# ADE7753.net
KiCad netlist of a schematic drawn in Altium Designer
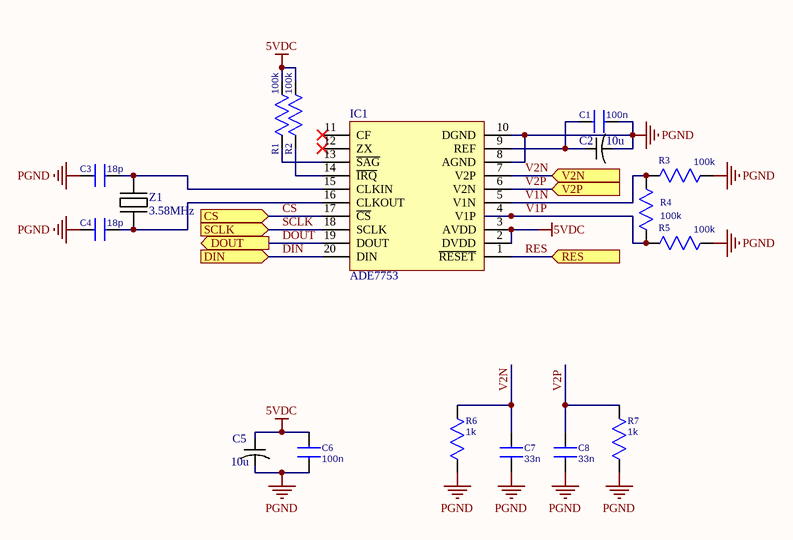
[diagram p0: ADE7753.SchDoc]

(export (version "E")
  (design (tool "Eeschema 10.0.6"))
  (components
    (comp (ref "C1")
      (value "100n")
      (footprint "C_0603")
      (description "Capacitor")
      (libsource (lib "AX_Altium_v2.3") (part "C0603"))
    )
    (comp (ref "C2")
      (value "10u")
      (footprint "TANTALUM_CAP_SIZE_A")
      (description "Tantalum Capacitor")
      (libsource (lib "BublykIntegratedLibrary") (part "Tantalum Capacitor"))
    )
    (comp (ref "C3")
      (value "18p")
      (footprint "C_0603")
      (description "Capacitor")
      (libsource (lib "AX_Altium_v2.3") (part "C0603"))
    )
    (comp (ref "C4")
      (value "18p")
      (footprint "C_0603")
      (description "Capacitor")
      (libsource (lib "AX_Altium_v2.3") (part "C0603"))
    )
    (comp (ref "C5")
      (value "10u")
      (footprint "TANTALUM_CAP_SIZE_A")
      (description "Tantalum Capacitor")
      (libsource (lib "") (part "Tantalum Capacitor_1"))
    )
    (comp (ref "C6")
      (value "100n")
      (footprint "C_0603")
      (description "Capacitor")
      (libsource (lib "AX_Altium_v2.3") (part "C0603"))
    )
    (comp (ref "C7")
      (value "33n")
      (footprint "C_0603")
      (description "Capacitor")
      (libsource (lib "AX_Altium_v2.3") (part "C0603"))
    )
    (comp (ref "C8")
      (value "33n")
      (footprint "C_0603")
      (description "Capacitor")
      (libsource (lib "AX_Altium_v2.3") (part "C0603"))
    )
    (comp (ref "IC1")
      (value "ADE7753")
      (footprint "SOP-20")
      (description "Data Acquisition ADC/DAC")
      (libsource (lib "SmartOutletIntegratedLibrary") (part "ADE7753ARSZ"))
    )
    (comp (ref "R1")
      (value "100k")
      (footprint "R_0603")
      (description "Resistor")
      (libsource (lib "AX_Altium_v2.3") (part "R0603"))
    )
    (comp (ref "R2")
      (value "100k")
      (footprint "R_0603")
      (description "Resistor")
      (libsource (lib "AX_Altium_v2.3") (part "R0603"))
    )
    (comp (ref "R3")
      (value "100k")
      (footprint "R_0603")
      (description "Resistor")
      (libsource (lib "AX_Altium_v2.3") (part "R0603"))
    )
    (comp (ref "R4")
      (value "100k")
      (footprint "R_0603")
      (description "Resistor")
      (libsource (lib "AX_Altium_v2.3") (part "R0603"))
    )
    (comp (ref "R5")
      (value "100k")
      (footprint "R_0603")
      (description "Resistor")
      (libsource (lib "AX_Altium_v2.3") (part "R0603"))
    )
    (comp (ref "R6")
      (value "1k")
      (footprint "R_0603")
      (description "Resistor")
      (libsource (lib "AX_Altium_v2.3") (part "R0603"))
    )
    (comp (ref "R7")
      (value "1k")
      (footprint "R_0805")
      (description "Resistor")
      (libsource (lib "AX_Altium_v2.3") (part "R0805"))
    )
    (comp (ref "Z1")
      (value "3.58MHz")
      (footprint "HC-49")
      (description "Quartz resonator")
      (libsource (lib "Light_Music_Integrated_Library") (part "XTAL"))
    )
  )
  (nets
    (net (code "1") (name "/CS") (class "Default")
      (node (ref "IC1") (pin "17") (pinfunction "~{CS}_17") (pintype "passive"))
    )
    (net (code "2") (name "/DIN") (class "Default")
      (node (ref "IC1") (pin "20") (pinfunction "DIN_20") (pintype "passive"))
    )
    (net (code "3") (name "/DOUT") (class "Default")
      (node (ref "IC1") (pin "19") (pinfunction "DOUT_19") (pintype "passive"))
    )
    (net (code "4") (name "/RES") (class "Default")
      (node (ref "IC1") (pin "1") (pinfunction "~{RESET}_1") (pintype "passive"))
    )
    (net (code "5") (name "/SCLK") (class "Default")
      (node (ref "IC1") (pin "18") (pinfunction "SCLK_18") (pintype "passive"))
    )
    (net (code "6") (name "/V1N") (class "Default")
      (node (ref "IC1") (pin "5") (pinfunction "V1N_5") (pintype "passive"))
      (node (ref "R3") (pin "2") (pintype "passive"))
      (node (ref "R4") (pin "2") (pintype "passive"))
    )
    (net (code "7") (name "/V1P") (class "Default")
      (node (ref "IC1") (pin "4") (pinfunction "V1P_4") (pintype "passive"))
      (node (ref "R4") (pin "1") (pintype "passive"))
      (node (ref "R5") (pin "2") (pintype "passive"))
    )
    (net (code "8") (name "/V2N") (class "Default")
      (node (ref "C7") (pin "2") (pintype "passive"))
      (node (ref "IC1") (pin "7") (pinfunction "V2P_7") (pintype "passive"))
      (node (ref "R6") (pin "1") (pintype "passive"))
    )
    (net (code "9") (name "/V2P") (class "Default")
      (node (ref "C8") (pin "2") (pintype "passive"))
      (node (ref "IC1") (pin "6") (pinfunction "V2N_6") (pintype "passive"))
      (node (ref "R7") (pin "1") (pintype "passive"))
    )
    (net (code "10") (name "5VDC") (class "Default")
      (node (ref "C5") (pin "1") (pinfunction "1_1") (pintype "passive"))
      (node (ref "C6") (pin "2") (pintype "passive"))
      (node (ref "IC1") (pin "2") (pinfunction "DVDD_2") (pintype "passive"))
      (node (ref "IC1") (pin "3") (pinfunction "AVDD_3") (pintype "passive"))
      (node (ref "R1") (pin "2") (pintype "passive"))
      (node (ref "R2") (pin "2") (pintype "passive"))
    )
    (net (code "11") (name "Net-(IC1-CLKIN)") (class "Default")
      (node (ref "C3") (pin "2") (pintype "passive"))
      (node (ref "IC1") (pin "15") (pinfunction "CLKIN_15") (pintype "passive"))
      (node (ref "Z1") (pin "2") (pinfunction "2_2") (pintype "passive"))
    )
    (net (code "12") (name "Net-(IC1-CLKOUT)") (class "Default")
      (node (ref "C4") (pin "2") (pintype "passive"))
      (node (ref "IC1") (pin "16") (pinfunction "CLKOUT_16") (pintype "passive"))
      (node (ref "Z1") (pin "1") (pinfunction "1_1") (pintype "passive"))
    )
    (net (code "13") (name "Net-(IC1-REF)") (class "Default")
      (node (ref "C1") (pin "1") (pintype "passive"))
      (node (ref "C2") (pin "1") (pinfunction "1_1") (pintype "passive"))
      (node (ref "IC1") (pin "9") (pinfunction "REF_9") (pintype "passive"))
    )
    (net (code "14") (name "Net-(IC1-~{IRQ})") (class "Default")
      (node (ref "IC1") (pin "14") (pinfunction "~{IRQ}_14") (pintype "passive"))
      (node (ref "R2") (pin "1") (pintype "passive"))
    )
    (net (code "15") (name "Net-(IC1-~{SAG})") (class "Default")
      (node (ref "IC1") (pin "13") (pinfunction "~{SAG}_13") (pintype "passive"))
      (node (ref "R1") (pin "1") (pintype "passive"))
    )
    (net (code "16") (name "PGND") (class "Default")
      (node (ref "C1") (pin "2") (pintype "passive"))
      (node (ref "C2") (pin "2") (pinfunction "2_2") (pintype "passive"))
      (node (ref "C3") (pin "1") (pintype "passive"))
      (node (ref "C4") (pin "1") (pintype "passive"))
      (node (ref "C5") (pin "2") (pinfunction "2_2") (pintype "passive"))
      (node (ref "C6") (pin "1") (pintype "passive"))
      (node (ref "C7") (pin "1") (pintype "passive"))
      (node (ref "C8") (pin "1") (pintype "passive"))
      (node (ref "IC1") (pin "10") (pinfunction "DGND_10") (pintype "passive"))
      (node (ref "IC1") (pin "8") (pinfunction "AGND_8") (pintype "passive"))
      (node (ref "R3") (pin "1") (pintype "passive"))
      (node (ref "R5") (pin "1") (pintype "passive"))
      (node (ref "R6") (pin "2") (pintype "passive"))
      (node (ref "R7") (pin "2") (pintype "passive"))
    )
    (net (code "17") (name "unconnected-(IC1-CF-Pad11)") (class "Default")
      (node (ref "IC1") (pin "11") (pinfunction "CF_11") (pintype "passive+no_connect"))
    )
    (net (code "18") (name "unconnected-(IC1-ZX-Pad12)") (class "Default")
      (node (ref "IC1") (pin "12") (pinfunction "ZX_12") (pintype "passive+no_connect"))
    )
  )
)
